# buttonPCB_schematic.net
KiCad netlist of a schematic drawn in EAGLE
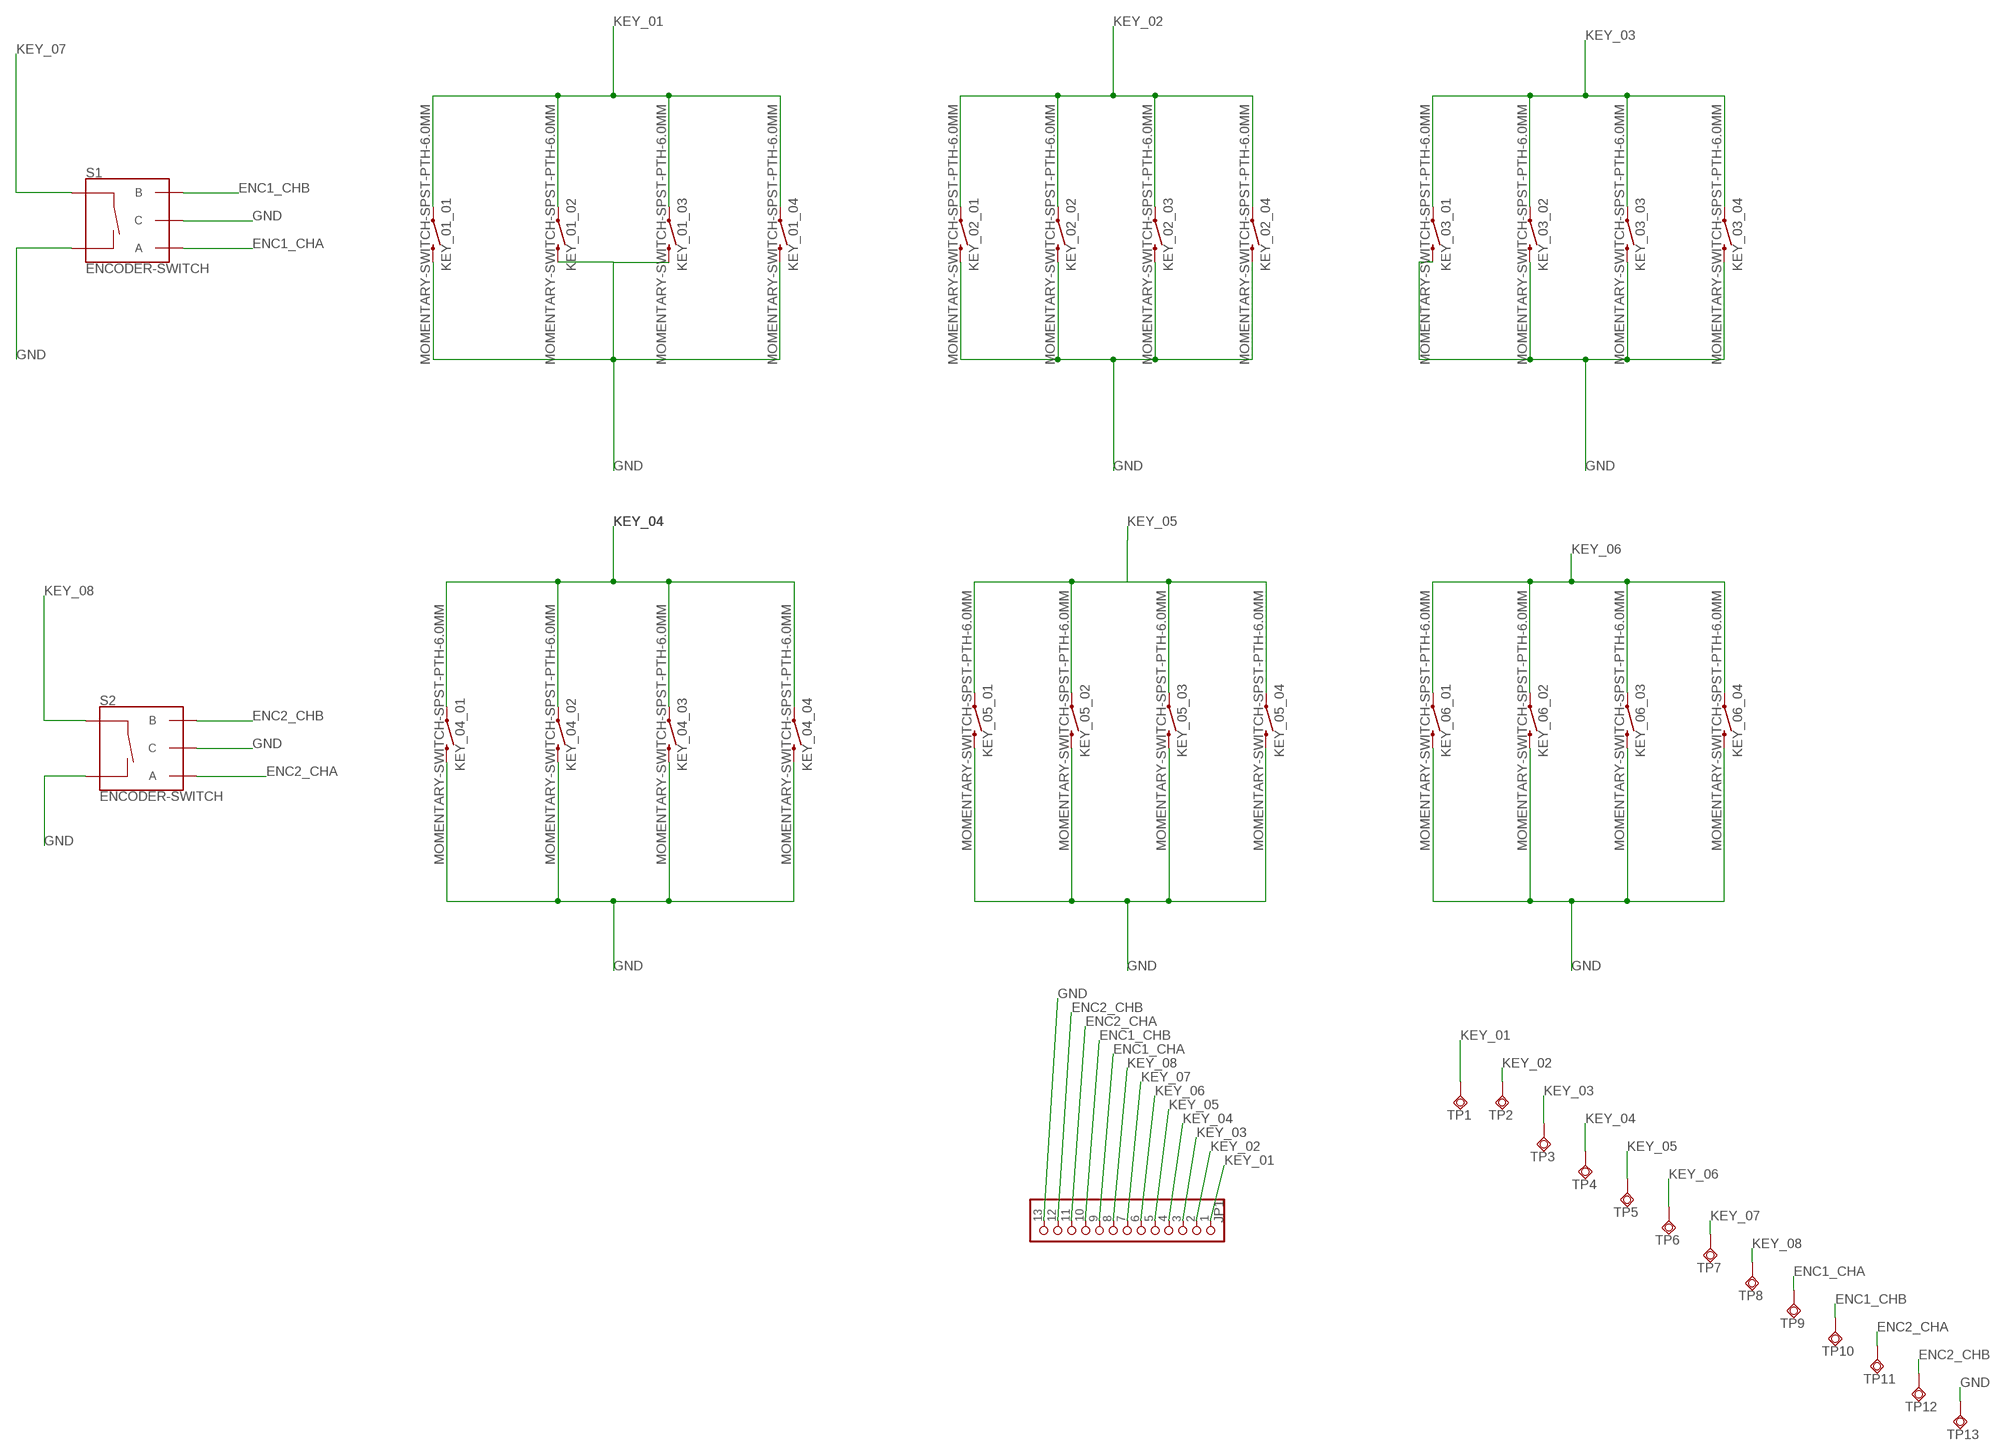
[diagram p0: schematic, sheet 1]

(export (version "E")
  (design (tool "Eeschema 10.0.6"))
  (components
    (comp (ref "JP1")
      (value "PINHD-1X13")
      (footprint "eagle-import:1X13")
      (libsource (lib "eagle-import") (part "PINHD-1X13"))
    )
    (comp (ref "KEY_01_01")
      (value "MOMENTARY-SWITCH-SPST-PTH-6.0MM")
      (footprint "eagle-import:TACTILE_SWITCH_PTH_6.0MM")
      (libsource (lib "eagle-import") (part "MOMENTARY-SWITCH-SPST-PTH-6.0MM"))
    )
    (comp (ref "KEY_01_02")
      (value "MOMENTARY-SWITCH-SPST-PTH-6.0MM")
      (footprint "eagle-import:TACTILE_SWITCH_PTH_6.0MM")
      (libsource (lib "eagle-import") (part "MOMENTARY-SWITCH-SPST-PTH-6.0MM"))
    )
    (comp (ref "KEY_01_03")
      (value "MOMENTARY-SWITCH-SPST-PTH-6.0MM")
      (footprint "eagle-import:TACTILE_SWITCH_PTH_6.0MM")
      (libsource (lib "eagle-import") (part "MOMENTARY-SWITCH-SPST-PTH-6.0MM"))
    )
    (comp (ref "KEY_01_04")
      (value "MOMENTARY-SWITCH-SPST-PTH-6.0MM")
      (footprint "eagle-import:TACTILE_SWITCH_PTH_6.0MM")
      (libsource (lib "eagle-import") (part "MOMENTARY-SWITCH-SPST-PTH-6.0MM"))
    )
    (comp (ref "KEY_02_01")
      (value "MOMENTARY-SWITCH-SPST-PTH-6.0MM")
      (footprint "eagle-import:TACTILE_SWITCH_PTH_6.0MM")
      (libsource (lib "eagle-import") (part "MOMENTARY-SWITCH-SPST-PTH-6.0MM"))
    )
    (comp (ref "KEY_02_02")
      (value "MOMENTARY-SWITCH-SPST-PTH-6.0MM")
      (footprint "eagle-import:TACTILE_SWITCH_PTH_6.0MM")
      (libsource (lib "eagle-import") (part "MOMENTARY-SWITCH-SPST-PTH-6.0MM"))
    )
    (comp (ref "KEY_02_03")
      (value "MOMENTARY-SWITCH-SPST-PTH-6.0MM")
      (footprint "eagle-import:TACTILE_SWITCH_PTH_6.0MM")
      (libsource (lib "eagle-import") (part "MOMENTARY-SWITCH-SPST-PTH-6.0MM"))
    )
    (comp (ref "KEY_02_04")
      (value "MOMENTARY-SWITCH-SPST-PTH-6.0MM")
      (footprint "eagle-import:TACTILE_SWITCH_PTH_6.0MM")
      (libsource (lib "eagle-import") (part "MOMENTARY-SWITCH-SPST-PTH-6.0MM"))
    )
    (comp (ref "KEY_03_01")
      (value "MOMENTARY-SWITCH-SPST-PTH-6.0MM")
      (footprint "eagle-import:TACTILE_SWITCH_PTH_6.0MM")
      (libsource (lib "eagle-import") (part "MOMENTARY-SWITCH-SPST-PTH-6.0MM"))
    )
    (comp (ref "KEY_03_02")
      (value "MOMENTARY-SWITCH-SPST-PTH-6.0MM")
      (footprint "eagle-import:TACTILE_SWITCH_PTH_6.0MM")
      (libsource (lib "eagle-import") (part "MOMENTARY-SWITCH-SPST-PTH-6.0MM"))
    )
    (comp (ref "KEY_03_03")
      (value "MOMENTARY-SWITCH-SPST-PTH-6.0MM")
      (footprint "eagle-import:TACTILE_SWITCH_PTH_6.0MM")
      (libsource (lib "eagle-import") (part "MOMENTARY-SWITCH-SPST-PTH-6.0MM"))
    )
    (comp (ref "KEY_03_04")
      (value "MOMENTARY-SWITCH-SPST-PTH-6.0MM")
      (footprint "eagle-import:TACTILE_SWITCH_PTH_6.0MM")
      (libsource (lib "eagle-import") (part "MOMENTARY-SWITCH-SPST-PTH-6.0MM"))
    )
    (comp (ref "KEY_04_01")
      (value "MOMENTARY-SWITCH-SPST-PTH-6.0MM")
      (footprint "eagle-import:TACTILE_SWITCH_PTH_6.0MM")
      (libsource (lib "eagle-import") (part "MOMENTARY-SWITCH-SPST-PTH-6.0MM"))
    )
    (comp (ref "KEY_04_02")
      (value "MOMENTARY-SWITCH-SPST-PTH-6.0MM")
      (footprint "eagle-import:TACTILE_SWITCH_PTH_6.0MM")
      (libsource (lib "eagle-import") (part "MOMENTARY-SWITCH-SPST-PTH-6.0MM"))
    )
    (comp (ref "KEY_04_03")
      (value "MOMENTARY-SWITCH-SPST-PTH-6.0MM")
      (footprint "eagle-import:TACTILE_SWITCH_PTH_6.0MM")
      (libsource (lib "eagle-import") (part "MOMENTARY-SWITCH-SPST-PTH-6.0MM"))
    )
    (comp (ref "KEY_04_04")
      (value "MOMENTARY-SWITCH-SPST-PTH-6.0MM")
      (footprint "eagle-import:TACTILE_SWITCH_PTH_6.0MM")
      (libsource (lib "eagle-import") (part "MOMENTARY-SWITCH-SPST-PTH-6.0MM"))
    )
    (comp (ref "KEY_05_01")
      (value "MOMENTARY-SWITCH-SPST-PTH-6.0MM")
      (footprint "eagle-import:TACTILE_SWITCH_PTH_6.0MM")
      (libsource (lib "eagle-import") (part "MOMENTARY-SWITCH-SPST-PTH-6.0MM"))
    )
    (comp (ref "KEY_05_02")
      (value "MOMENTARY-SWITCH-SPST-PTH-6.0MM")
      (footprint "eagle-import:TACTILE_SWITCH_PTH_6.0MM")
      (libsource (lib "eagle-import") (part "MOMENTARY-SWITCH-SPST-PTH-6.0MM"))
    )
    (comp (ref "KEY_05_03")
      (value "MOMENTARY-SWITCH-SPST-PTH-6.0MM")
      (footprint "eagle-import:TACTILE_SWITCH_PTH_6.0MM")
      (libsource (lib "eagle-import") (part "MOMENTARY-SWITCH-SPST-PTH-6.0MM"))
    )
    (comp (ref "KEY_05_04")
      (value "MOMENTARY-SWITCH-SPST-PTH-6.0MM")
      (footprint "eagle-import:TACTILE_SWITCH_PTH_6.0MM")
      (libsource (lib "eagle-import") (part "MOMENTARY-SWITCH-SPST-PTH-6.0MM"))
    )
    (comp (ref "KEY_06_01")
      (value "MOMENTARY-SWITCH-SPST-PTH-6.0MM")
      (footprint "eagle-import:TACTILE_SWITCH_PTH_6.0MM")
      (libsource (lib "eagle-import") (part "MOMENTARY-SWITCH-SPST-PTH-6.0MM"))
    )
    (comp (ref "KEY_06_02")
      (value "MOMENTARY-SWITCH-SPST-PTH-6.0MM")
      (footprint "eagle-import:TACTILE_SWITCH_PTH_6.0MM")
      (libsource (lib "eagle-import") (part "MOMENTARY-SWITCH-SPST-PTH-6.0MM"))
    )
    (comp (ref "KEY_06_03")
      (value "MOMENTARY-SWITCH-SPST-PTH-6.0MM")
      (footprint "eagle-import:TACTILE_SWITCH_PTH_6.0MM")
      (libsource (lib "eagle-import") (part "MOMENTARY-SWITCH-SPST-PTH-6.0MM"))
    )
    (comp (ref "KEY_06_04")
      (value "MOMENTARY-SWITCH-SPST-PTH-6.0MM")
      (footprint "eagle-import:TACTILE_SWITCH_PTH_6.0MM")
      (libsource (lib "eagle-import") (part "MOMENTARY-SWITCH-SPST-PTH-6.0MM"))
    )
    (comp (ref "S1")
      (value "ENCODER-SWITCH")
      (footprint "eagle-import:ROTARY_ENC_PLAIN")
      (libsource (lib "eagle-import") (part "ENCODER-SWITCH"))
    )
    (comp (ref "S2")
      (value "ENCODER-SWITCH")
      (footprint "eagle-import:ROTARY_ENC_PLAIN")
      (libsource (lib "eagle-import") (part "ENCODER-SWITCH"))
    )
    (comp (ref "TP1")
      (value "TPSQTP18SQ")
      (footprint "eagle-import:TP18SQ")
      (libsource (lib "eagle-import") (part "TPSQTP18SQ"))
    )
    (comp (ref "TP2")
      (value "TPSQTP18SQ")
      (footprint "eagle-import:TP18SQ")
      (libsource (lib "eagle-import") (part "TPSQTP18SQ"))
    )
    (comp (ref "TP3")
      (value "TPSQTP18SQ")
      (footprint "eagle-import:TP18SQ")
      (libsource (lib "eagle-import") (part "TPSQTP18SQ"))
    )
    (comp (ref "TP4")
      (value "TPSQTP18SQ")
      (footprint "eagle-import:TP18SQ")
      (libsource (lib "eagle-import") (part "TPSQTP18SQ"))
    )
    (comp (ref "TP5")
      (value "TPSQTP18SQ")
      (footprint "eagle-import:TP18SQ")
      (libsource (lib "eagle-import") (part "TPSQTP18SQ"))
    )
    (comp (ref "TP6")
      (value "TPSQTP18SQ")
      (footprint "eagle-import:TP18SQ")
      (libsource (lib "eagle-import") (part "TPSQTP18SQ"))
    )
    (comp (ref "TP7")
      (value "TPSQTP18SQ")
      (footprint "eagle-import:TP18SQ")
      (libsource (lib "eagle-import") (part "TPSQTP18SQ"))
    )
    (comp (ref "TP8")
      (value "TPSQTP18SQ")
      (footprint "eagle-import:TP18SQ")
      (libsource (lib "eagle-import") (part "TPSQTP18SQ"))
    )
    (comp (ref "TP9")
      (value "TPSQTP18SQ")
      (footprint "eagle-import:TP18SQ")
      (libsource (lib "eagle-import") (part "TPSQTP18SQ"))
    )
    (comp (ref "TP10")
      (value "TPSQTP18SQ")
      (footprint "eagle-import:TP18SQ")
      (libsource (lib "eagle-import") (part "TPSQTP18SQ"))
    )
    (comp (ref "TP11")
      (value "TPSQTP18SQ")
      (footprint "eagle-import:TP18SQ")
      (libsource (lib "eagle-import") (part "TPSQTP18SQ"))
    )
    (comp (ref "TP12")
      (value "TPSQTP18SQ")
      (footprint "eagle-import:TP18SQ")
      (libsource (lib "eagle-import") (part "TPSQTP18SQ"))
    )
    (comp (ref "TP13")
      (value "TPSQTP18SQ")
      (footprint "eagle-import:TP18SQ")
      (libsource (lib "eagle-import") (part "TPSQTP18SQ"))
    )
  )
  (nets
    (net (code "1") (name "/ENC1_CHA") (class "Default")
      (node (ref "JP1") (pin "9") (pinfunction "9_9") (pintype "passive"))
      (node (ref "S1") (pin "A") (pinfunction "A_A") (pintype "bidirectional"))
      (node (ref "TP9") (pin "TP") (pinfunction "TP_TP") (pintype "input"))
    )
    (net (code "2") (name "/ENC1_CHB") (class "Default")
      (node (ref "JP1") (pin "10") (pinfunction "10_10") (pintype "passive"))
      (node (ref "S1") (pin "B") (pinfunction "B_B") (pintype "bidirectional"))
      (node (ref "TP10") (pin "TP") (pinfunction "TP_TP") (pintype "input"))
    )
    (net (code "3") (name "/ENC2_CHA") (class "Default")
      (node (ref "JP1") (pin "11") (pinfunction "11_11") (pintype "passive"))
      (node (ref "S2") (pin "A") (pinfunction "A_A") (pintype "bidirectional"))
      (node (ref "TP11") (pin "TP") (pinfunction "TP_TP") (pintype "input"))
    )
    (net (code "4") (name "/ENC2_CHB") (class "Default")
      (node (ref "JP1") (pin "12") (pinfunction "12_12") (pintype "passive"))
      (node (ref "S2") (pin "B") (pinfunction "B_B") (pintype "bidirectional"))
      (node (ref "TP12") (pin "TP") (pinfunction "TP_TP") (pintype "input"))
    )
    (net (code "5") (name "/GND") (class "Default")
      (node (ref "JP1") (pin "13") (pinfunction "13_13") (pintype "passive"))
      (node (ref "KEY_01_01") (pin "3") (pinfunction "2_3") (pintype "passive"))
      (node (ref "KEY_01_02") (pin "3") (pinfunction "2_3") (pintype "passive"))
      (node (ref "KEY_01_03") (pin "3") (pinfunction "2_3") (pintype "passive"))
      (node (ref "KEY_01_04") (pin "3") (pinfunction "2_3") (pintype "passive"))
      (node (ref "KEY_02_01") (pin "3") (pinfunction "2_3") (pintype "passive"))
      (node (ref "KEY_02_02") (pin "3") (pinfunction "2_3") (pintype "passive"))
      (node (ref "KEY_02_03") (pin "3") (pinfunction "2_3") (pintype "passive"))
      (node (ref "KEY_02_04") (pin "3") (pinfunction "2_3") (pintype "passive"))
      (node (ref "KEY_03_01") (pin "3") (pinfunction "2_3") (pintype "passive"))
      (node (ref "KEY_03_02") (pin "3") (pinfunction "2_3") (pintype "passive"))
      (node (ref "KEY_03_03") (pin "3") (pinfunction "2_3") (pintype "passive"))
      (node (ref "KEY_03_04") (pin "3") (pinfunction "2_3") (pintype "passive"))
      (node (ref "KEY_04_01") (pin "3") (pinfunction "2_3") (pintype "passive"))
      (node (ref "KEY_04_02") (pin "3") (pinfunction "2_3") (pintype "passive"))
      (node (ref "KEY_04_03") (pin "3") (pinfunction "2_3") (pintype "passive"))
      (node (ref "KEY_04_04") (pin "3") (pinfunction "2_3") (pintype "passive"))
      (node (ref "KEY_05_01") (pin "3") (pinfunction "2_3") (pintype "passive"))
      (node (ref "KEY_05_02") (pin "3") (pinfunction "2_3") (pintype "passive"))
      (node (ref "KEY_05_03") (pin "3") (pinfunction "2_3") (pintype "passive"))
      (node (ref "KEY_05_04") (pin "3") (pinfunction "2_3") (pintype "passive"))
      (node (ref "KEY_06_01") (pin "3") (pinfunction "2_3") (pintype "passive"))
      (node (ref "KEY_06_02") (pin "3") (pinfunction "2_3") (pintype "passive"))
      (node (ref "KEY_06_03") (pin "3") (pinfunction "2_3") (pintype "passive"))
      (node (ref "KEY_06_04") (pin "3") (pinfunction "2_3") (pintype "passive"))
      (node (ref "S1") (pin "C") (pinfunction "C_C") (pintype "bidirectional"))
      (node (ref "S1") (pin "SW-") (pinfunction "SW-_SW-") (pintype "bidirectional"))
      (node (ref "S2") (pin "C") (pinfunction "C_C") (pintype "bidirectional"))
      (node (ref "S2") (pin "SW-") (pinfunction "SW-_SW-") (pintype "bidirectional"))
      (node (ref "TP13") (pin "TP") (pinfunction "TP_TP") (pintype "input"))
    )
    (net (code "6") (name "/KEY_01") (class "Default")
      (node (ref "JP1") (pin "1") (pinfunction "1_1") (pintype "passive"))
      (node (ref "KEY_01_01") (pin "1") (pinfunction "1_1") (pintype "passive"))
      (node (ref "KEY_01_02") (pin "1") (pinfunction "1_1") (pintype "passive"))
      (node (ref "KEY_01_03") (pin "1") (pinfunction "1_1") (pintype "passive"))
      (node (ref "KEY_01_04") (pin "1") (pinfunction "1_1") (pintype "passive"))
      (node (ref "TP1") (pin "TP") (pinfunction "TP_TP") (pintype "input"))
    )
    (net (code "7") (name "/KEY_02") (class "Default")
      (node (ref "JP1") (pin "2") (pinfunction "2_2") (pintype "passive"))
      (node (ref "KEY_02_01") (pin "1") (pinfunction "1_1") (pintype "passive"))
      (node (ref "KEY_02_02") (pin "1") (pinfunction "1_1") (pintype "passive"))
      (node (ref "KEY_02_03") (pin "1") (pinfunction "1_1") (pintype "passive"))
      (node (ref "KEY_02_04") (pin "1") (pinfunction "1_1") (pintype "passive"))
      (node (ref "TP2") (pin "TP") (pinfunction "TP_TP") (pintype "input"))
    )
    (net (code "8") (name "/KEY_03") (class "Default")
      (node (ref "JP1") (pin "3") (pinfunction "3_3") (pintype "passive"))
      (node (ref "KEY_03_01") (pin "1") (pinfunction "1_1") (pintype "passive"))
      (node (ref "KEY_03_02") (pin "1") (pinfunction "1_1") (pintype "passive"))
      (node (ref "KEY_03_03") (pin "1") (pinfunction "1_1") (pintype "passive"))
      (node (ref "KEY_03_04") (pin "1") (pinfunction "1_1") (pintype "passive"))
      (node (ref "TP3") (pin "TP") (pinfunction "TP_TP") (pintype "input"))
    )
    (net (code "9") (name "/KEY_04") (class "Default")
      (node (ref "JP1") (pin "4") (pinfunction "4_4") (pintype "passive"))
      (node (ref "KEY_04_01") (pin "1") (pinfunction "1_1") (pintype "passive"))
      (node (ref "KEY_04_02") (pin "1") (pinfunction "1_1") (pintype "passive"))
      (node (ref "KEY_04_03") (pin "1") (pinfunction "1_1") (pintype "passive"))
      (node (ref "KEY_04_04") (pin "1") (pinfunction "1_1") (pintype "passive"))
      (node (ref "TP4") (pin "TP") (pinfunction "TP_TP") (pintype "input"))
    )
    (net (code "10") (name "/KEY_05") (class "Default")
      (node (ref "JP1") (pin "5") (pinfunction "5_5") (pintype "passive"))
      (node (ref "KEY_05_01") (pin "1") (pinfunction "1_1") (pintype "passive"))
      (node (ref "KEY_05_02") (pin "1") (pinfunction "1_1") (pintype "passive"))
      (node (ref "KEY_05_03") (pin "1") (pinfunction "1_1") (pintype "passive"))
      (node (ref "KEY_05_04") (pin "1") (pinfunction "1_1") (pintype "passive"))
      (node (ref "TP5") (pin "TP") (pinfunction "TP_TP") (pintype "input"))
    )
    (net (code "11") (name "/KEY_06") (class "Default")
      (node (ref "JP1") (pin "6") (pinfunction "6_6") (pintype "passive"))
      (node (ref "KEY_06_01") (pin "1") (pinfunction "1_1") (pintype "passive"))
      (node (ref "KEY_06_02") (pin "1") (pinfunction "1_1") (pintype "passive"))
      (node (ref "KEY_06_03") (pin "1") (pinfunction "1_1") (pintype "passive"))
      (node (ref "KEY_06_04") (pin "1") (pinfunction "1_1") (pintype "passive"))
      (node (ref "TP6") (pin "TP") (pinfunction "TP_TP") (pintype "input"))
    )
    (net (code "12") (name "/KEY_07") (class "Default")
      (node (ref "JP1") (pin "7") (pinfunction "7_7") (pintype "passive"))
      (node (ref "S1") (pin "SW+") (pinfunction "SW+_SW+") (pintype "bidirectional"))
      (node (ref "TP7") (pin "TP") (pinfunction "TP_TP") (pintype "input"))
    )
    (net (code "13") (name "/KEY_08") (class "Default")
      (node (ref "JP1") (pin "8") (pinfunction "8_8") (pintype "passive"))
      (node (ref "S2") (pin "SW+") (pinfunction "SW+_SW+") (pintype "bidirectional"))
      (node (ref "TP8") (pin "TP") (pinfunction "TP_TP") (pintype "input"))
    )
  )
)
